# untitled.net
KiCad netlist of a schematic drawn in EAGLE
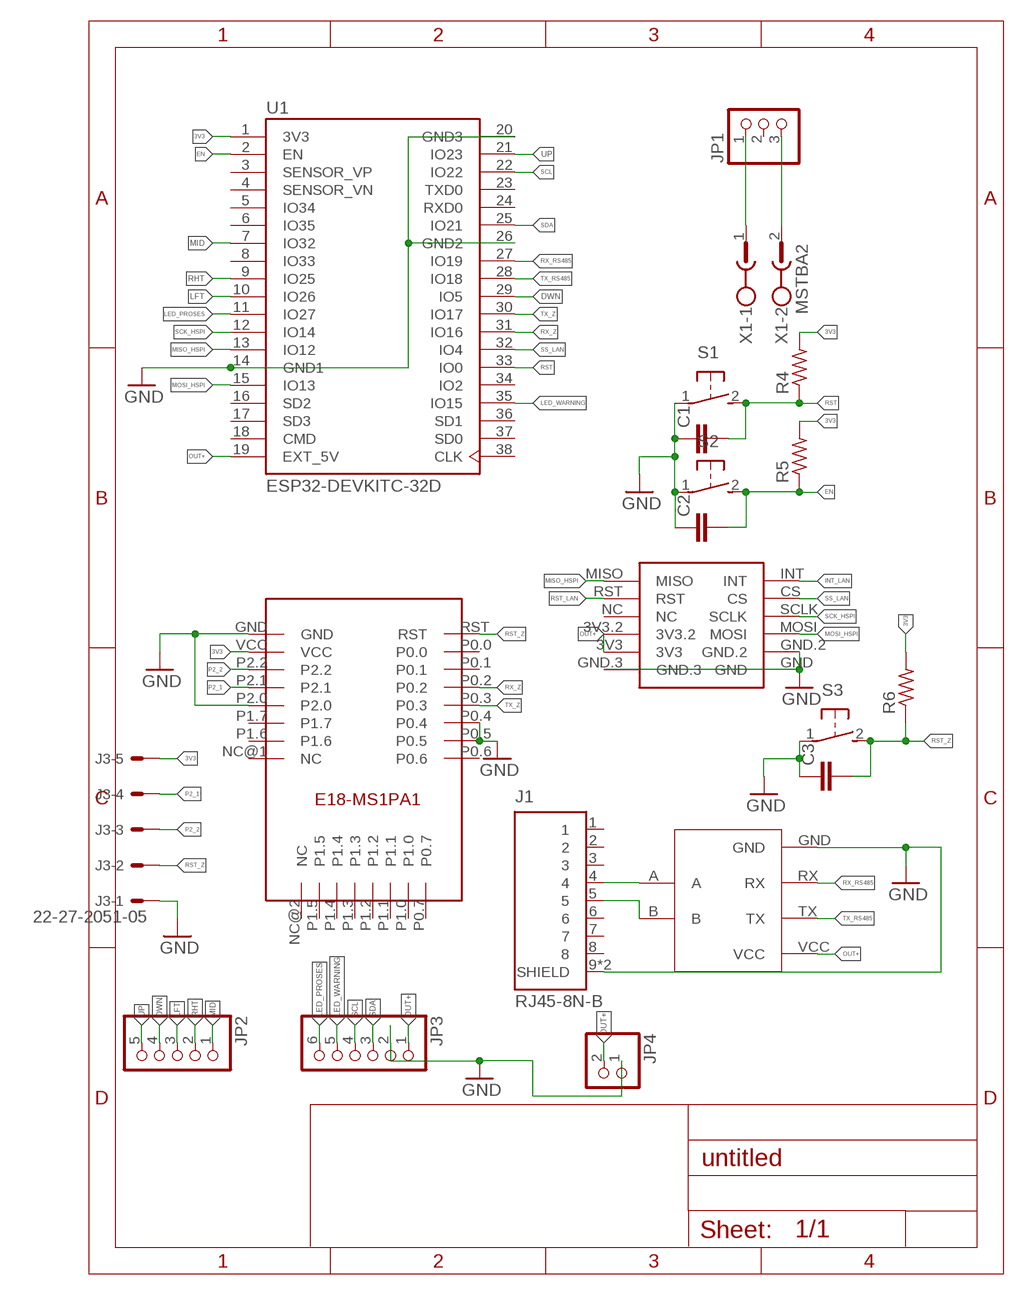
[diagram p0: schematic, sheet 1]

(export (version "E")
  (design (tool "Eeschema 10.0.6"))
  (components
    (comp (ref "C1")
      (value "C-EUC0805K")
      (footprint "eagle-import:C0805K")
      (libsource (lib "eagle-import") (part "C-EUC0805K"))
    )
    (comp (ref "C2")
      (value "C-EUC0805K")
      (footprint "eagle-import:C0805K")
      (libsource (lib "eagle-import") (part "C-EUC0805K"))
    )
    (comp (ref "C3")
      (value "C-EUC0805K")
      (footprint "eagle-import:C0805K")
      (libsource (lib "eagle-import") (part "C-EUC0805K"))
    )
    (comp (ref "J1")
      (value "RJ45-8N-B")
      (footprint "eagle-import:TE_RJ45-8N-B")
      (fields (field (name "MF") "TE Connectivity"))
      (libsource (lib "eagle-import") (part "RJ45-8N-B"))
    )
    (comp (ref "J3")
      (value "22-27-2051-05")
      (footprint "eagle-import:6410-05")
      (fields (field (name "MF") "MOLEX"))
      (libsource (lib "eagle-import") (part "22-?-0527-2051"))
    )
    (comp (ref "JP1")
      (value "PINHD-1X3")
      (footprint "eagle-import:1X03")
      (libsource (lib "eagle-import") (part "PINHD-1X3"))
    )
    (comp (ref "JP2")
      (value "PINHD-1X5")
      (footprint "eagle-import:1X05")
      (libsource (lib "eagle-import") (part "PINHD-1X5"))
    )
    (comp (ref "JP3")
      (value "PINHD-1X6")
      (footprint "eagle-import:1X06")
      (libsource (lib "eagle-import") (part "PINHD-1X6"))
    )
    (comp (ref "JP4")
      (value "PINHD-1X2")
      (footprint "eagle-import:1X02")
      (libsource (lib "eagle-import") (part "PINHD-1X2"))
    )
    (comp (ref "R4")
      (value "R-US_M0805")
      (footprint "eagle-import:M0805")
      (libsource (lib "eagle-import") (part "R-US_M0805"))
    )
    (comp (ref "R5")
      (value "R-US_M0805")
      (footprint "eagle-import:M0805")
      (libsource (lib "eagle-import") (part "R-US_M0805"))
    )
    (comp (ref "R6")
      (value "R-US_M0805")
      (footprint "eagle-import:M0805")
      (libsource (lib "eagle-import") (part "R-US_M0805"))
    )
    (comp (ref "S1")
      (value "31-XX")
      (footprint "eagle-import:B3F-31XX")
      (fields (field (name "MPN") "B3F-3100"))
      (libsource (lib "eagle-import") (part "31-XX"))
    )
    (comp (ref "S2")
      (value "31-XX")
      (footprint "eagle-import:B3F-31XX")
      (fields (field (name "MPN") "B3F-3100"))
      (libsource (lib "eagle-import") (part "31-XX"))
    )
    (comp (ref "S3")
      (value "31-XX")
      (footprint "eagle-import:B3F-31XX")
      (fields (field (name "MPN") "B3F-3100"))
      (libsource (lib "eagle-import") (part "31-XX"))
    )
    (comp (ref "TTL-RS1")
      (value "TTL-RS485")
      (footprint "eagle-import:TTL-RS485")
      (libsource (lib "eagle-import") (part "TTL-RS485"))
    )
    (comp (ref "U$1")
      (value "E18-MS1PA1IPX")
      (footprint "eagle-import:E18-MS1PA1-IPX")
      (libsource (lib "eagle-import") (part "E18-MS1PA1IPX"))
    )
    (comp (ref "U$2")
      (value "MINI_W5500")
      (footprint "eagle-import:MINI_W5500")
      (libsource (lib "eagle-import") (part "MINI_W5500"))
    )
    (comp (ref "U1")
      (value "ESP32-DEVKITC-32D")
      (footprint "eagle-import:MODULE_ESP32-DEVKITC-32D")
      (fields (field (name "MF") "Espressif Systems"))
      (libsource (lib "eagle-import") (part "ESP32-DEVKITC-32D"))
    )
    (comp (ref "X1")
      (value "MSTBA2")
      (footprint "eagle-import:MSTBA2")
      (fields (field (name "MF") "FARNELL") (field (name "MPN") "1757242"))
      (libsource (lib "eagle-import") (part "MSTBA2"))
    )
  )
  (nets
    (net (code "1") (name "3V3") (class "Default")
      (node (ref "J3") (pin "5") (pinfunction "S_5") (pintype "passive"))
      (node (ref "R4") (pin "2") (pinfunction "2_2") (pintype "passive"))
      (node (ref "R5") (pin "2") (pinfunction "2_2") (pintype "passive"))
      (node (ref "R6") (pin "2") (pinfunction "2_2") (pintype "passive"))
      (node (ref "U$1") (pin "VCC") (pinfunction "VCC_VCC") (pintype "bidirectional"))
      (node (ref "U1") (pin "1") (pinfunction "3V3_1") (pintype "power_in"))
    )
    (net (code "2") (name "DWN") (class "Default")
      (node (ref "JP2") (pin "4") (pinfunction "4_4") (pintype "passive"))
      (node (ref "U1") (pin "29") (pinfunction "IO5_29") (pintype "bidirectional"))
    )
    (net (code "3") (name "EN") (class "Default")
      (node (ref "C2") (pin "2") (pinfunction "2_2") (pintype "passive"))
      (node (ref "R5") (pin "1") (pinfunction "1_1") (pintype "passive"))
      (node (ref "S2") (pin "2") (pinfunction "S_2") (pintype "passive"))
      (node (ref "U1") (pin "2") (pinfunction "EN_2") (pintype "input"))
    )
    (net (code "4") (name "GND") (class "Default")
      (node (ref "C1") (pin "1") (pinfunction "1_1") (pintype "passive"))
      (node (ref "C2") (pin "1") (pinfunction "1_1") (pintype "passive"))
      (node (ref "C3") (pin "1") (pinfunction "1_1") (pintype "passive"))
      (node (ref "J1") (pin "10") (pinfunction "SHIELD_10") (pintype "passive"))
      (node (ref "J1") (pin "9") (pinfunction "SHIELD_9") (pintype "passive"))
      (node (ref "J3") (pin "1") (pinfunction "S_1") (pintype "passive"))
      (node (ref "JP3") (pin "2") (pinfunction "2_2") (pintype "passive"))
      (node (ref "JP4") (pin "1") (pinfunction "1_1") (pintype "passive"))
      (node (ref "S1") (pin "1") (pinfunction "P_1") (pintype "passive"))
      (node (ref "S2") (pin "1") (pinfunction "P_1") (pintype "passive"))
      (node (ref "S3") (pin "1") (pinfunction "P_1") (pintype "passive"))
      (node (ref "TTL-RS1") (pin "GND") (pinfunction "GND_GND") (pintype "bidirectional"))
      (node (ref "U$1") (pin "GND") (pinfunction "GND_GND") (pintype "bidirectional"))
      (node (ref "U$1") (pin "P0.4") (pinfunction "P0.4_P0.4") (pintype "bidirectional"))
      (node (ref "U$1") (pin "P0.5") (pinfunction "P0.5_P0.5") (pintype "bidirectional"))
      (node (ref "U$1") (pin "P2.0") (pinfunction "P2.0_P2.0") (pintype "bidirectional"))
      (node (ref "U$2") (pin "GND") (pinfunction "GND_GND") (pintype "bidirectional"))
      (node (ref "U$2") (pin "GND.2") (pinfunction "GND.2_GND.2") (pintype "bidirectional"))
      (node (ref "U$2") (pin "GND.3") (pinfunction "GND.3_GND.3") (pintype "bidirectional"))
      (node (ref "U1") (pin "14") (pinfunction "GND1_14") (pintype "power_in"))
      (node (ref "U1") (pin "20") (pinfunction "GND3_20") (pintype "power_in"))
      (node (ref "U1") (pin "26") (pinfunction "GND2_26") (pintype "power_in"))
    )
    (net (code "5") (name "INT_LAN") (class "Default")
      (node (ref "U$2") (pin "INT") (pinfunction "INT_INT") (pintype "bidirectional"))
    )
    (net (code "6") (name "LED_PROSES") (class "Default")
      (node (ref "JP3") (pin "6") (pinfunction "6_6") (pintype "passive"))
      (node (ref "U1") (pin "11") (pinfunction "IO27_11") (pintype "bidirectional"))
    )
    (net (code "7") (name "LED_WARNING") (class "Default")
      (node (ref "JP3") (pin "5") (pinfunction "5_5") (pintype "passive"))
      (node (ref "U1") (pin "35") (pinfunction "IO15_35") (pintype "bidirectional"))
    )
    (net (code "8") (name "LFT") (class "Default")
      (node (ref "JP2") (pin "3") (pinfunction "3_3") (pintype "passive"))
      (node (ref "U1") (pin "10") (pinfunction "IO26_10") (pintype "bidirectional"))
    )
    (net (code "9") (name "MID") (class "Default")
      (node (ref "JP2") (pin "1") (pinfunction "1_1") (pintype "passive"))
      (node (ref "U1") (pin "7") (pinfunction "IO32_7") (pintype "bidirectional"))
    )
    (net (code "10") (name "MISO_HSPI") (class "Default")
      (node (ref "U$2") (pin "MISO") (pinfunction "MISO_MISO") (pintype "bidirectional"))
      (node (ref "U1") (pin "13") (pinfunction "IO12_13") (pintype "bidirectional"))
    )
    (net (code "11") (name "MOSI_HSPI") (class "Default")
      (node (ref "U$2") (pin "MOSI") (pinfunction "MOSI_MOSI") (pintype "bidirectional"))
      (node (ref "U1") (pin "15") (pinfunction "IO13_15") (pintype "bidirectional"))
    )
    (net (code "12") (name "Net-(J1-Pad4)") (class "Default")
      (node (ref "J1") (pin "4") (pinfunction "4_4") (pintype "passive"))
      (node (ref "TTL-RS1") (pin "A") (pinfunction "A_A") (pintype "bidirectional"))
    )
    (net (code "13") (name "Net-(J1-Pad5)") (class "Default")
      (node (ref "J1") (pin "5") (pinfunction "5_5") (pintype "passive"))
      (node (ref "TTL-RS1") (pin "B") (pinfunction "B_B") (pintype "bidirectional"))
    )
    (net (code "14") (name "Net-(JP1-Pad1)") (class "Default")
      (node (ref "JP1") (pin "1") (pinfunction "1_1") (pintype "passive"))
      (node (ref "X1") (pin "1") (pinfunction "1_1") (pintype "passive"))
    )
    (net (code "15") (name "Net-(X1B-1)") (class "Default")
      (node (ref "JP1") (pin "3") (pinfunction "3_3") (pintype "passive"))
      (node (ref "X1") (pin "2") (pinfunction "1_2") (pintype "passive"))
    )
    (net (code "16") (name "OUT+") (class "Default")
      (node (ref "JP3") (pin "1") (pinfunction "1_1") (pintype "passive"))
      (node (ref "JP4") (pin "2") (pinfunction "2_2") (pintype "passive"))
      (node (ref "TTL-RS1") (pin "VCC") (pinfunction "VCC_VCC") (pintype "bidirectional"))
      (node (ref "U$2") (pin "3V3") (pinfunction "3V3_3V3") (pintype "bidirectional"))
      (node (ref "U$2") (pin "3V3.2") (pinfunction "3V3.2_3V3.2") (pintype "bidirectional"))
      (node (ref "U1") (pin "19") (pinfunction "EXT_5V_19") (pintype "power_in"))
    )
    (net (code "17") (name "P2_1") (class "Default")
      (node (ref "J3") (pin "4") (pinfunction "S_4") (pintype "passive"))
      (node (ref "U$1") (pin "P2.1") (pinfunction "P2.1_P2.1") (pintype "bidirectional"))
    )
    (net (code "18") (name "P2_2") (class "Default")
      (node (ref "J3") (pin "3") (pinfunction "S_3") (pintype "passive"))
      (node (ref "U$1") (pin "P2.2") (pinfunction "P2.2_P2.2") (pintype "bidirectional"))
    )
    (net (code "19") (name "RHT") (class "Default")
      (node (ref "JP2") (pin "2") (pinfunction "2_2") (pintype "passive"))
      (node (ref "U1") (pin "9") (pinfunction "IO25_9") (pintype "bidirectional"))
    )
    (net (code "20") (name "RST") (class "Default")
      (node (ref "C1") (pin "2") (pinfunction "2_2") (pintype "passive"))
      (node (ref "R4") (pin "1") (pinfunction "1_1") (pintype "passive"))
      (node (ref "S1") (pin "2") (pinfunction "S_2") (pintype "passive"))
      (node (ref "U1") (pin "33") (pinfunction "IO0_33") (pintype "bidirectional"))
    )
    (net (code "21") (name "RST_LAN") (class "Default")
      (node (ref "U$2") (pin "RST") (pinfunction "RST_RST") (pintype "bidirectional"))
    )
    (net (code "22") (name "RST_Z") (class "Default")
      (node (ref "C3") (pin "2") (pinfunction "2_2") (pintype "passive"))
      (node (ref "J3") (pin "2") (pinfunction "S_2") (pintype "passive"))
      (node (ref "R6") (pin "1") (pinfunction "1_1") (pintype "passive"))
      (node (ref "S3") (pin "2") (pinfunction "S_2") (pintype "passive"))
      (node (ref "U$1") (pin "RST") (pinfunction "RST_RST") (pintype "bidirectional"))
    )
    (net (code "23") (name "RX_RS485") (class "Default")
      (node (ref "TTL-RS1") (pin "RX") (pinfunction "RX_RX") (pintype "bidirectional"))
      (node (ref "U1") (pin "27") (pinfunction "IO19_27") (pintype "bidirectional"))
    )
    (net (code "24") (name "RX_Z") (class "Default")
      (node (ref "U$1") (pin "P0.2") (pinfunction "P0.2_P0.2") (pintype "bidirectional"))
      (node (ref "U1") (pin "31") (pinfunction "IO16_31") (pintype "bidirectional"))
    )
    (net (code "25") (name "SCK_HSPI") (class "Default")
      (node (ref "U$2") (pin "SCLK") (pinfunction "SCLK_SCLK") (pintype "bidirectional"))
      (node (ref "U1") (pin "12") (pinfunction "IO14_12") (pintype "bidirectional"))
    )
    (net (code "26") (name "SCL") (class "Default")
      (node (ref "JP3") (pin "4") (pinfunction "4_4") (pintype "passive"))
      (node (ref "U1") (pin "22") (pinfunction "IO22_22") (pintype "bidirectional"))
    )
    (net (code "27") (name "SDA") (class "Default")
      (node (ref "JP3") (pin "3") (pinfunction "3_3") (pintype "passive"))
      (node (ref "U1") (pin "25") (pinfunction "IO21_25") (pintype "bidirectional"))
    )
    (net (code "28") (name "SS_LAN") (class "Default")
      (node (ref "U$2") (pin "CS") (pinfunction "CS_CS") (pintype "bidirectional"))
      (node (ref "U1") (pin "32") (pinfunction "IO4_32") (pintype "bidirectional"))
    )
    (net (code "29") (name "TX_RS485") (class "Default")
      (node (ref "TTL-RS1") (pin "TX") (pinfunction "TX_TX") (pintype "bidirectional"))
      (node (ref "U1") (pin "28") (pinfunction "IO18_28") (pintype "bidirectional"))
    )
    (net (code "30") (name "TX_Z") (class "Default")
      (node (ref "U$1") (pin "P0.3") (pinfunction "P0.3_P0.3") (pintype "bidirectional"))
      (node (ref "U1") (pin "30") (pinfunction "IO17_30") (pintype "bidirectional"))
    )
    (net (code "31") (name "UP") (class "Default")
      (node (ref "JP2") (pin "5") (pinfunction "5_5") (pintype "passive"))
      (node (ref "U1") (pin "21") (pinfunction "IO23_21") (pintype "bidirectional"))
    )
    (net (code "32") (name "unconnected-(J1-Pad1)") (class "Default")
      (node (ref "J1") (pin "1") (pinfunction "1_1") (pintype "passive"))
    )
    (net (code "33") (name "unconnected-(J1-Pad2)") (class "Default")
      (node (ref "J1") (pin "2") (pinfunction "2_2") (pintype "passive"))
    )
    (net (code "34") (name "unconnected-(J1-Pad3)") (class "Default")
      (node (ref "J1") (pin "3") (pinfunction "3_3") (pintype "passive"))
    )
    (net (code "35") (name "unconnected-(J1-Pad6)") (class "Default")
      (node (ref "J1") (pin "6") (pinfunction "6_6") (pintype "passive"))
    )
    (net (code "36") (name "unconnected-(J1-Pad7)") (class "Default")
      (node (ref "J1") (pin "7") (pinfunction "7_7") (pintype "passive"))
    )
    (net (code "37") (name "unconnected-(J1-Pad8)") (class "Default")
      (node (ref "J1") (pin "8") (pinfunction "8_8") (pintype "passive"))
    )
    (net (code "38") (name "unconnected-(JP1-Pad2)") (class "Default")
      (node (ref "JP1") (pin "2") (pinfunction "2_2") (pintype "passive"))
    )
    (net (code "39") (name "unconnected-(U$1-NC-PadNC@1)") (class "Default")
      (node (ref "U$1") (pin "NC@1") (pinfunction "NC_NC@1") (pintype "bidirectional"))
    )
    (net (code "40") (name "unconnected-(U$1-NC-PadNC@2)") (class "Default")
      (node (ref "U$1") (pin "NC@2") (pinfunction "NC_NC@2") (pintype "bidirectional"))
    )
    (net (code "41") (name "unconnected-(U$1-PadP0.0)") (class "Default")
      (node (ref "U$1") (pin "P0.0") (pinfunction "P0.0_P0.0") (pintype "bidirectional"))
    )
    (net (code "42") (name "unconnected-(U$1-PadP0.1)") (class "Default")
      (node (ref "U$1") (pin "P0.1") (pinfunction "P0.1_P0.1") (pintype "bidirectional"))
    )
    (net (code "43") (name "unconnected-(U$1-PadP0.6)") (class "Default")
      (node (ref "U$1") (pin "P0.6") (pinfunction "P0.6_P0.6") (pintype "bidirectional"))
    )
    (net (code "44") (name "unconnected-(U$1-PadP0.7)") (class "Default")
      (node (ref "U$1") (pin "P0.7") (pinfunction "P0.7_P0.7") (pintype "bidirectional"))
    )
    (net (code "45") (name "unconnected-(U$1-PadP1.0)") (class "Default")
      (node (ref "U$1") (pin "P1.0") (pinfunction "P1.0_P1.0") (pintype "bidirectional"))
    )
    (net (code "46") (name "unconnected-(U$1-PadP1.1)") (class "Default")
      (node (ref "U$1") (pin "P1.1") (pinfunction "P1.1_P1.1") (pintype "bidirectional"))
    )
    (net (code "47") (name "unconnected-(U$1-PadP1.2)") (class "Default")
      (node (ref "U$1") (pin "P1.2") (pinfunction "P1.2_P1.2") (pintype "bidirectional"))
    )
    (net (code "48") (name "unconnected-(U$1-PadP1.3)") (class "Default")
      (node (ref "U$1") (pin "P1.3") (pinfunction "P1.3_P1.3") (pintype "bidirectional"))
    )
    (net (code "49") (name "unconnected-(U$1-PadP1.4)") (class "Default")
      (node (ref "U$1") (pin "P1.4") (pinfunction "P1.4_P1.4") (pintype "bidirectional"))
    )
    (net (code "50") (name "unconnected-(U$1-PadP1.5)") (class "Default")
      (node (ref "U$1") (pin "P1.5") (pinfunction "P1.5_P1.5") (pintype "bidirectional"))
    )
    (net (code "51") (name "unconnected-(U$1-PadP1.6)") (class "Default")
      (node (ref "U$1") (pin "P1.6") (pinfunction "P1.6_P1.6") (pintype "bidirectional"))
    )
    (net (code "52") (name "unconnected-(U$1-PadP1.7)") (class "Default")
      (node (ref "U$1") (pin "P1.7") (pinfunction "P1.7_P1.7") (pintype "bidirectional"))
    )
    (net (code "53") (name "unconnected-(U$2-PadNC)") (class "Default")
      (node (ref "U$2") (pin "NC") (pinfunction "NC_NC") (pintype "bidirectional"))
    )
    (net (code "54") (name "unconnected-(U1-CLK-Pad38)") (class "Default")
      (node (ref "U1") (pin "38") (pinfunction "CLK_38") (pintype "input"))
    )
    (net (code "55") (name "unconnected-(U1-CMD-Pad18)") (class "Default")
      (node (ref "U1") (pin "18") (pinfunction "CMD_18") (pintype "bidirectional"))
    )
    (net (code "56") (name "unconnected-(U1-IO2-Pad34)") (class "Default")
      (node (ref "U1") (pin "34") (pinfunction "IO2_34") (pintype "bidirectional"))
    )
    (net (code "57") (name "unconnected-(U1-IO33-Pad8)") (class "Default")
      (node (ref "U1") (pin "8") (pinfunction "IO33_8") (pintype "bidirectional"))
    )
    (net (code "58") (name "unconnected-(U1-IO34-Pad5)") (class "Default")
      (node (ref "U1") (pin "5") (pinfunction "IO34_5") (pintype "bidirectional"))
    )
    (net (code "59") (name "unconnected-(U1-IO35-Pad6)") (class "Default")
      (node (ref "U1") (pin "6") (pinfunction "IO35_6") (pintype "bidirectional"))
    )
    (net (code "60") (name "unconnected-(U1-RXD0-Pad24)") (class "Default")
      (node (ref "U1") (pin "24") (pinfunction "RXD0_24") (pintype "input"))
    )
    (net (code "61") (name "unconnected-(U1-SD0-Pad37)") (class "Default")
      (node (ref "U1") (pin "37") (pinfunction "SD0_37") (pintype "bidirectional"))
    )
    (net (code "62") (name "unconnected-(U1-SD1-Pad36)") (class "Default")
      (node (ref "U1") (pin "36") (pinfunction "SD1_36") (pintype "bidirectional"))
    )
    (net (code "63") (name "unconnected-(U1-SD2-Pad16)") (class "Default")
      (node (ref "U1") (pin "16") (pinfunction "SD2_16") (pintype "bidirectional"))
    )
    (net (code "64") (name "unconnected-(U1-SD3-Pad17)") (class "Default")
      (node (ref "U1") (pin "17") (pinfunction "SD3_17") (pintype "bidirectional"))
    )
    (net (code "65") (name "unconnected-(U1-SENSOR_VN-Pad4)") (class "Default")
      (node (ref "U1") (pin "4") (pinfunction "SENSOR_VN_4") (pintype "input"))
    )
    (net (code "66") (name "unconnected-(U1-SENSOR_VP-Pad3)") (class "Default")
      (node (ref "U1") (pin "3") (pinfunction "SENSOR_VP_3") (pintype "input"))
    )
    (net (code "67") (name "unconnected-(U1-TXD0-Pad23)") (class "Default")
      (node (ref "U1") (pin "23") (pinfunction "TXD0_23") (pintype "output"))
    )
  )
)
